# tqfp-sandwich-main.net
KiCad netlist of a schematic drawn in EAGLE
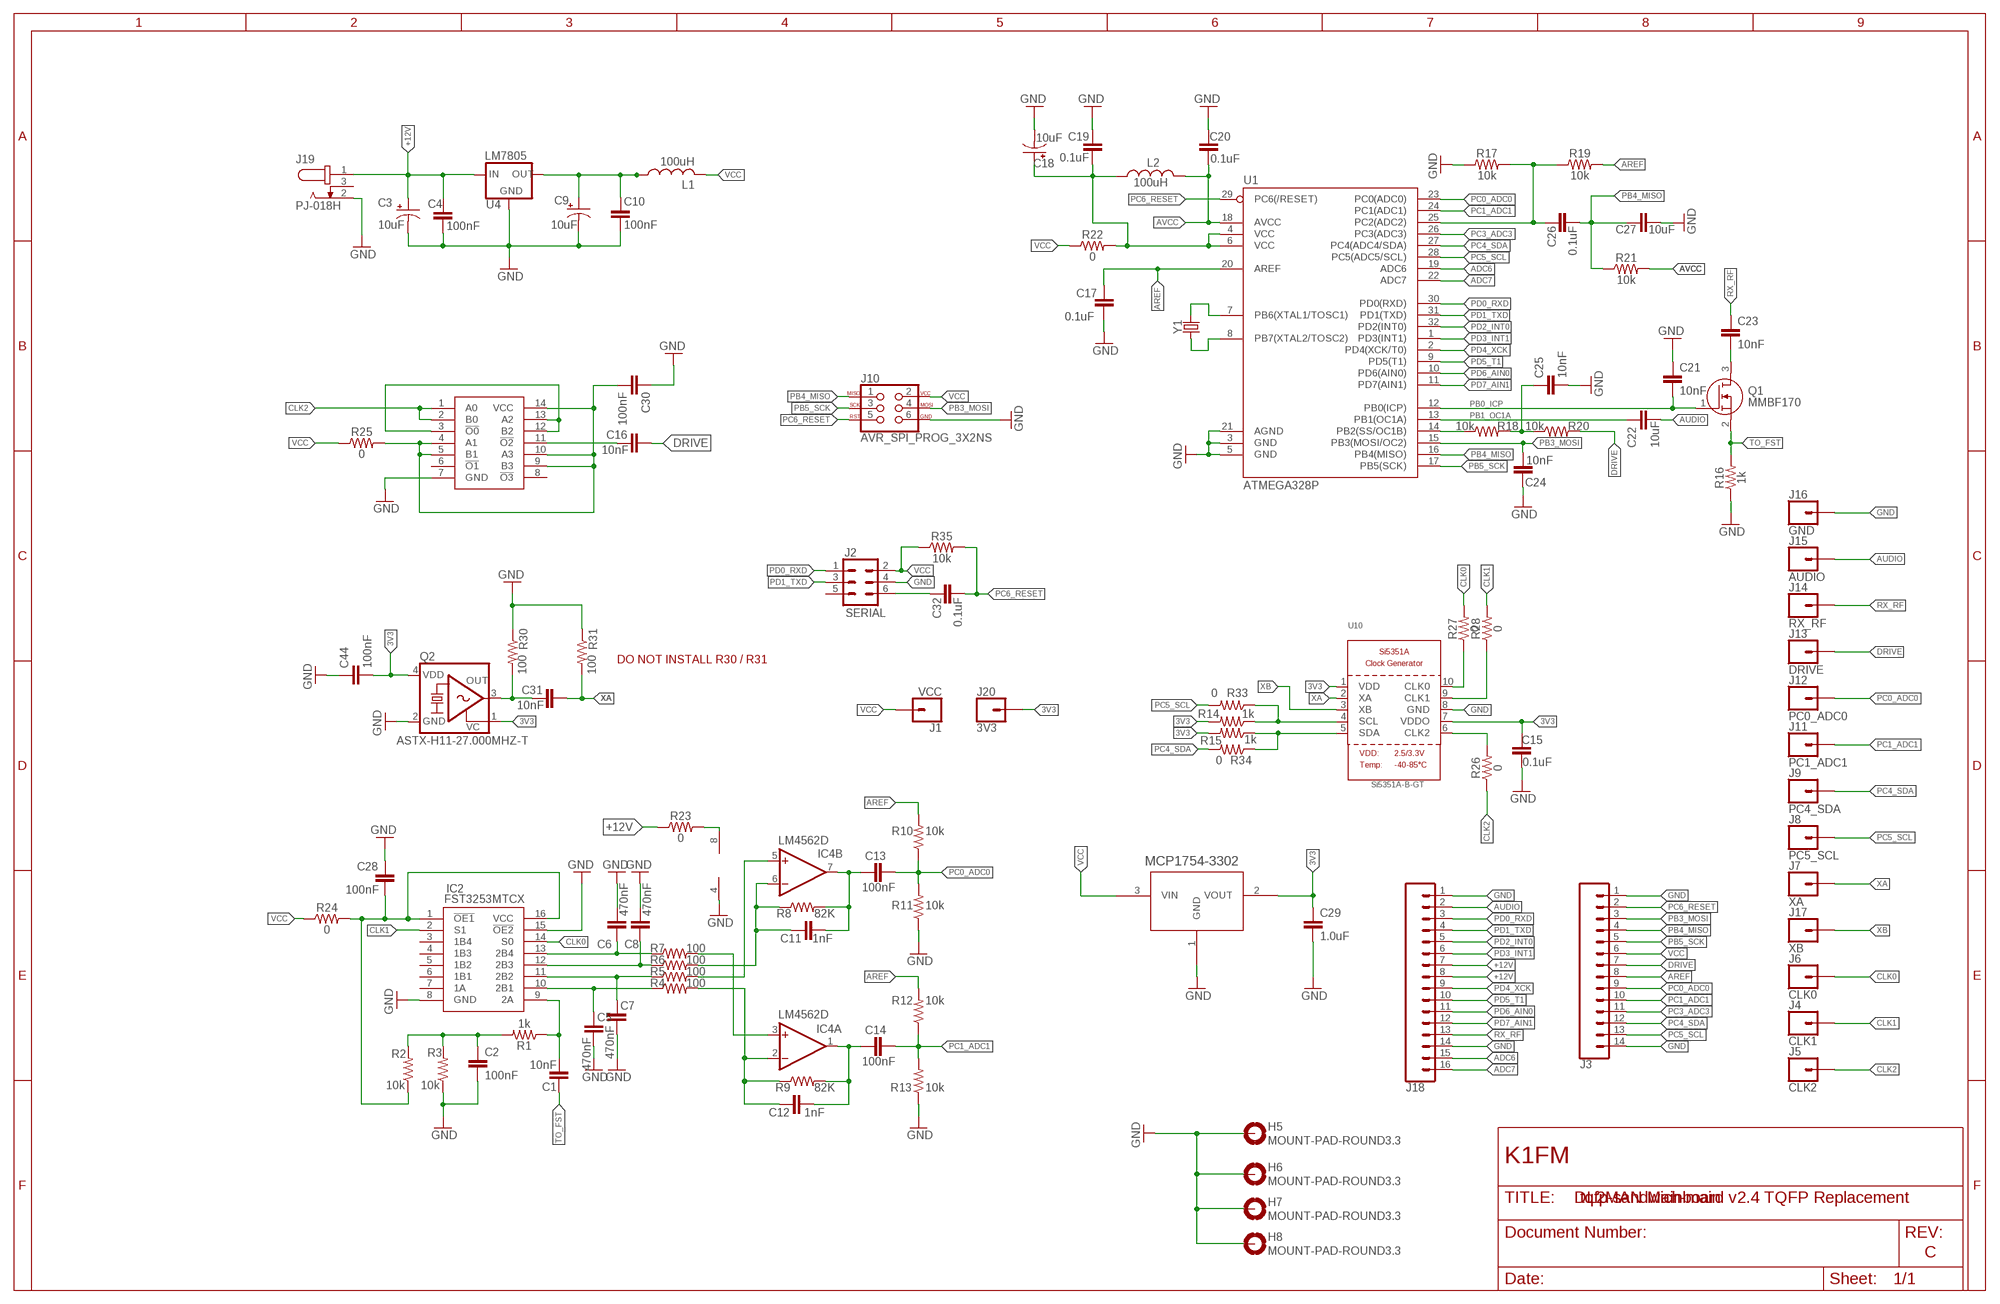
[diagram p0: schematic, sheet 1]

(export (version "E")
  (design (tool "Eeschema 10.0.6"))
  (components
    (comp (ref "C1")
      (value "10nF")
      (footprint "eagle-import:0603")
      (libsource (lib "eagle-import") (part "10NF-0603-50V-10%"))
    )
    (comp (ref "C2")
      (value "100nF")
      (footprint "eagle-import:0603")
      (libsource (lib "eagle-import") (part "10NF-0603-50V-10%"))
    )
    (comp (ref "C3")
      (value "10uF")
      (footprint "eagle-import:EIA3216")
      (libsource (lib "eagle-import") (part "10UF-POLAR-EIA3216-16V-10%(TANT)"))
    )
    (comp (ref "C4")
      (value "100nF")
      (footprint "eagle-import:0603")
      (libsource (lib "eagle-import") (part "10NF-0603-50V-10%"))
    )
    (comp (ref "C5")
      (value "470nF")
      (footprint "eagle-import:0603")
      (libsource (lib "eagle-import") (part "470PF-0603-50V-5%"))
    )
    (comp (ref "C6")
      (value "470nF")
      (footprint "eagle-import:0603")
      (libsource (lib "eagle-import") (part "470PF-0603-50V-5%"))
    )
    (comp (ref "C7")
      (value "470nF")
      (footprint "eagle-import:0603")
      (libsource (lib "eagle-import") (part "470PF-0603-50V-5%"))
    )
    (comp (ref "C8")
      (value "470nF")
      (footprint "eagle-import:0603")
      (libsource (lib "eagle-import") (part "470PF-0603-50V-5%"))
    )
    (comp (ref "C9")
      (value "10uF")
      (footprint "eagle-import:EIA3216")
      (libsource (lib "eagle-import") (part "10UF-POLAR-EIA3216-16V-10%(TANT)"))
    )
    (comp (ref "C10")
      (value "100nF")
      (footprint "eagle-import:0603")
      (libsource (lib "eagle-import") (part "10NF-0603-50V-10%"))
    )
    (comp (ref "C11")
      (value "1nF")
      (footprint "eagle-import:0603")
      (libsource (lib "eagle-import") (part "1.0NF/1000PF-0603-50V-10%"))
    )
    (comp (ref "C12")
      (value "1nF")
      (footprint "eagle-import:0603")
      (libsource (lib "eagle-import") (part "1.0NF/1000PF-0603-50V-10%"))
    )
    (comp (ref "C13")
      (value "100nF")
      (footprint "eagle-import:0603")
      (libsource (lib "eagle-import") (part "10NF-0603-50V-10%"))
    )
    (comp (ref "C14")
      (value "100nF")
      (footprint "eagle-import:0603")
      (libsource (lib "eagle-import") (part "10NF-0603-50V-10%"))
    )
    (comp (ref "C15")
      (value "0.1uF")
      (footprint "eagle-import:0603")
      (libsource (lib "eagle-import") (part "0.1UF-0603-25V-(+80/-20%)"))
    )
    (comp (ref "C16")
      (value "10nF")
      (footprint "eagle-import:0603")
      (libsource (lib "eagle-import") (part "10NF-0603-50V-10%"))
    )
    (comp (ref "C17")
      (value "0.1uF")
      (footprint "eagle-import:0603")
      (libsource (lib "eagle-import") (part "0.1UF-0603-25V-(+80/-20%)"))
    )
    (comp (ref "C18")
      (value "10uF")
      (footprint "eagle-import:EIA3216")
      (libsource (lib "eagle-import") (part "10UF-POLAR-EIA3216-16V-10%(TANT)"))
    )
    (comp (ref "C19")
      (value "0.1uF")
      (footprint "eagle-import:0603")
      (libsource (lib "eagle-import") (part "0.1UF-0603-25V-(+80/-20%)"))
    )
    (comp (ref "C20")
      (value "0.1uF")
      (footprint "eagle-import:0603")
      (libsource (lib "eagle-import") (part "0.1UF-0603-25V-(+80/-20%)"))
    )
    (comp (ref "C21")
      (value "10nF")
      (footprint "eagle-import:0603")
      (libsource (lib "eagle-import") (part "10NF-0603-50V-10%"))
    )
    (comp (ref "C22")
      (value "10uF")
      (footprint "eagle-import:0603")
      (libsource (lib "eagle-import") (part "10UF-0603-6.3V-20%"))
    )
    (comp (ref "C23")
      (value "10nF")
      (footprint "eagle-import:0603")
      (libsource (lib "eagle-import") (part "10NF-0603-50V-10%"))
    )
    (comp (ref "C24")
      (value "10nF")
      (footprint "eagle-import:0603")
      (libsource (lib "eagle-import") (part "10NF-0603-50V-10%"))
    )
    (comp (ref "C25")
      (value "10nF")
      (footprint "eagle-import:0603")
      (libsource (lib "eagle-import") (part "10NF-0603-50V-10%"))
    )
    (comp (ref "C26")
      (value "0.1uF")
      (footprint "eagle-import:0603")
      (libsource (lib "eagle-import") (part "0.1UF-0603-25V-(+80/-20%)"))
    )
    (comp (ref "C27")
      (value "10uF")
      (footprint "eagle-import:0603")
      (libsource (lib "eagle-import") (part "10NF-0603-50V-10%"))
    )
    (comp (ref "C28")
      (value "100nF")
      (footprint "eagle-import:0603")
      (libsource (lib "eagle-import") (part "10NF-0603-50V-10%"))
    )
    (comp (ref "C29")
      (value "1.0uF")
      (footprint "eagle-import:0603")
      (libsource (lib "eagle-import") (part "1.0UF-0603-16V-10%"))
    )
    (comp (ref "C30")
      (value "100nF")
      (footprint "eagle-import:0603")
      (libsource (lib "eagle-import") (part "10NF-0603-50V-10%"))
    )
    (comp (ref "C31")
      (value "10nF")
      (footprint "eagle-import:0603")
      (libsource (lib "eagle-import") (part "10NF-0603-50V-10%"))
    )
    (comp (ref "C32")
      (value "0.1uF")
      (footprint "eagle-import:0603")
      (libsource (lib "eagle-import") (part "0.1UF-0603-25V-(+80/-20%)"))
    )
    (comp (ref "C44")
      (value "100nF")
      (footprint "eagle-import:0603")
      (libsource (lib "eagle-import") (part "10NF-0603-50V-10%"))
    )
    (comp (ref "H5")
      (value "MOUNT-PAD-ROUND3.3")
      (footprint "eagle-import:3,3-PAD")
      (libsource (lib "eagle-import") (part "MOUNT-PAD-ROUND3.3"))
    )
    (comp (ref "H6")
      (value "MOUNT-PAD-ROUND3.3")
      (footprint "eagle-import:3,3-PAD")
      (libsource (lib "eagle-import") (part "MOUNT-PAD-ROUND3.3"))
    )
    (comp (ref "H7")
      (value "MOUNT-PAD-ROUND3.3")
      (footprint "eagle-import:3,3-PAD")
      (libsource (lib "eagle-import") (part "MOUNT-PAD-ROUND3.3"))
    )
    (comp (ref "H8")
      (value "MOUNT-PAD-ROUND3.3")
      (footprint "eagle-import:3,3-PAD")
      (libsource (lib "eagle-import") (part "MOUNT-PAD-ROUND3.3"))
    )
    (comp (ref "IC2")
      (value "FST3253MTCX")
      (footprint "eagle-import:SOP65P640X110-16N")
      (fields (field (name "MOUSER_PART_NUMBER") "512-FST3253MTCX"))
      (libsource (lib "eagle-import") (part "FST3253MTCX"))
    )
    (comp (ref "IC3")
      (value "74ACT00MTC")
      (footprint "eagle-import:SOP65P640X120-14N")
      (fields (field (name "MOUSER_PART_NUMBER") "512-74ACT00MTC"))
      (libsource (lib "eagle-import") (part "74ACT00MTC"))
    )
    (comp (ref "IC4")
      (value "LM4562D")
      (footprint "eagle-import:SO08")
      (libsource (lib "eagle-import") (part "LM4562D"))
    )
    (comp (ref "J1")
      (value "VCC")
      (footprint "eagle-import:1X01NS_KIT")
      (libsource (lib "eagle-import") (part "CONN_01PTH_NO_SILK_KIT"))
    )
    (comp (ref "J2")
      (value "SERIAL")
      (footprint "eagle-import:2X3")
      (libsource (lib "eagle-import") (part "CONN_03X2FEMALE"))
    )
    (comp (ref "J3")
      (value "CONN_14")
      (footprint "eagle-import:1X14")
      (libsource (lib "eagle-import") (part "CONN_14"))
    )
    (comp (ref "J4")
      (value "CLK1")
      (footprint "eagle-import:1X01_LONGPAD")
      (libsource (lib "eagle-import") (part "CONN_01PTH_LONGPAD"))
    )
    (comp (ref "J5")
      (value "CLK2")
      (footprint "eagle-import:1X01_LONGPAD")
      (libsource (lib "eagle-import") (part "CONN_01PTH_LONGPAD"))
    )
    (comp (ref "J6")
      (value "CLK0")
      (footprint "eagle-import:1X01_LONGPAD")
      (libsource (lib "eagle-import") (part "CONN_01PTH_LONGPAD"))
    )
    (comp (ref "J7")
      (value "XA")
      (footprint "eagle-import:1X01_LONGPAD")
      (libsource (lib "eagle-import") (part "CONN_01PTH_LONGPAD"))
    )
    (comp (ref "J8")
      (value "PC5_SCL")
      (footprint "eagle-import:1X01_LONGPAD")
      (libsource (lib "eagle-import") (part "CONN_01PTH_LONGPAD"))
    )
    (comp (ref "J9")
      (value "PC4_SDA")
      (footprint "eagle-import:1X01_LONGPAD")
      (libsource (lib "eagle-import") (part "CONN_01PTH_LONGPAD"))
    )
    (comp (ref "J10")
      (value "AVR_SPI_PROG_3X2NS")
      (footprint "eagle-import:2X3-NS")
      (libsource (lib "eagle-import") (part "AVR_SPI_PROG_3X2NS"))
    )
    (comp (ref "J11")
      (value "PC1_ADC1")
      (footprint "eagle-import:1X01_LONGPAD")
      (libsource (lib "eagle-import") (part "CONN_01PTH_LONGPAD"))
    )
    (comp (ref "J12")
      (value "PC0_ADC0")
      (footprint "eagle-import:1X01_LONGPAD")
      (libsource (lib "eagle-import") (part "CONN_01PTH_LONGPAD"))
    )
    (comp (ref "J13")
      (value "DRIVE")
      (footprint "eagle-import:1X01_LONGPAD")
      (libsource (lib "eagle-import") (part "CONN_01PTH_LONGPAD"))
    )
    (comp (ref "J14")
      (value "RX_RF")
      (footprint "eagle-import:1X01_LONGPAD")
      (libsource (lib "eagle-import") (part "CONN_01PTH_LONGPAD"))
    )
    (comp (ref "J15")
      (value "AUDIO")
      (footprint "eagle-import:1X01_LONGPAD")
      (libsource (lib "eagle-import") (part "CONN_01PTH_LONGPAD"))
    )
    (comp (ref "J16")
      (value "GND")
      (footprint "eagle-import:1X01_LONGPAD")
      (libsource (lib "eagle-import") (part "CONN_01PTH_LONGPAD"))
    )
    (comp (ref "J17")
      (value "XB")
      (footprint "eagle-import:1X01_LONGPAD")
      (libsource (lib "eagle-import") (part "CONN_01PTH_LONGPAD"))
    )
    (comp (ref "J18")
      (value "CONN_16")
      (footprint "eagle-import:1X16")
      (libsource (lib "eagle-import") (part "CONN_16"))
    )
    (comp (ref "J19")
      (value "PJ-018H")
      (footprint "eagle-import:CUI_PJ-018H")
      (fields (field (name "MANUFACTURER") "CUI INC"))
      (libsource (lib "eagle-import") (part "PJ-018H"))
    )
    (comp (ref "J20")
      (value "3V3")
      (footprint "eagle-import:1X01NS_KIT")
      (libsource (lib "eagle-import") (part "CONN_01PTH_NO_SILK_KIT"))
    )
    (comp (ref "L1")
      (value "100uH")
      (footprint "eagle-import:RESC0805_L")
      (libsource (lib "eagle-import") (part "INDUCTOR_0805_L"))
    )
    (comp (ref "L2")
      (value "100uH")
      (footprint "eagle-import:RESC0805_L")
      (libsource (lib "eagle-import") (part "INDUCTOR_0805_L"))
    )
    (comp (ref "Q1")
      (value "MMBF170")
      (footprint "eagle-import:SOT96P237X111-3N")
      (fields (field (name "MOUSER_PART_NUMBER") "512-MMBF170"))
      (libsource (lib "eagle-import") (part "MMBF170"))
    )
    (comp (ref "Q2")
      (value "ASTX-H11-27.000MHZ-T")
      (footprint "eagle-import:3.2X2.5_KXO-84")
      (libsource (lib "eagle-import") (part "KXO-VCXO-SINE-84"))
    )
    (comp (ref "R1")
      (value "1k")
      (footprint "eagle-import:0603")
      (libsource (lib "eagle-import") (part "1KOHM-0603-1/10W-1%"))
    )
    (comp (ref "R2")
      (value "10k")
      (footprint "eagle-import:0603")
      (libsource (lib "eagle-import") (part "10KOHM-0603-1/10W-1%"))
    )
    (comp (ref "R3")
      (value "10k")
      (footprint "eagle-import:0603")
      (libsource (lib "eagle-import") (part "10KOHM-0603-1/10W-1%"))
    )
    (comp (ref "R4")
      (value "100")
      (footprint "eagle-import:0603")
      (libsource (lib "eagle-import") (part "100OHM-0603-1/4W-5%"))
    )
    (comp (ref "R5")
      (value "100")
      (footprint "eagle-import:0603")
      (libsource (lib "eagle-import") (part "100OHM-0603-1/4W-5%"))
    )
    (comp (ref "R6")
      (value "100")
      (footprint "eagle-import:0603")
      (libsource (lib "eagle-import") (part "100OHM-0603-1/4W-5%"))
    )
    (comp (ref "R7")
      (value "100")
      (footprint "eagle-import:0603")
      (libsource (lib "eagle-import") (part "100OHM-0603-1/4W-5%"))
    )
    (comp (ref "R8")
      (value "82K")
      (footprint "eagle-import:0603")
      (libsource (lib "eagle-import") (part "82OHM-0603-1/10W-1%"))
    )
    (comp (ref "R9")
      (value "82K")
      (footprint "eagle-import:0603")
      (libsource (lib "eagle-import") (part "82OHM-0603-1/10W-1%"))
    )
    (comp (ref "R10")
      (value "10k")
      (footprint "eagle-import:0603")
      (libsource (lib "eagle-import") (part "10KOHM-0603-1/10W-1%"))
    )
    (comp (ref "R11")
      (value "10k")
      (footprint "eagle-import:0603")
      (libsource (lib "eagle-import") (part "10KOHM-0603-1/10W-1%"))
    )
    (comp (ref "R12")
      (value "10k")
      (footprint "eagle-import:0603")
      (libsource (lib "eagle-import") (part "10KOHM-0603-1/10W-1%"))
    )
    (comp (ref "R13")
      (value "10k")
      (footprint "eagle-import:0603")
      (libsource (lib "eagle-import") (part "10KOHM-0603-1/10W-1%"))
    )
    (comp (ref "R14")
      (value "1k")
      (footprint "eagle-import:0603")
      (libsource (lib "eagle-import") (part "1KOHM-0603-1/10W-1%"))
    )
    (comp (ref "R15")
      (value "1k")
      (footprint "eagle-import:0603")
      (libsource (lib "eagle-import") (part "1KOHM-0603-1/10W-1%"))
    )
    (comp (ref "R16")
      (value "1k")
      (footprint "eagle-import:0603")
      (libsource (lib "eagle-import") (part "1KOHM-0603-1/10W-1%"))
    )
    (comp (ref "R17")
      (value "10k")
      (footprint "eagle-import:0603")
      (libsource (lib "eagle-import") (part "10KOHM-0603-1/10W-1%"))
    )
    (comp (ref "R18")
      (value "10k")
      (footprint "eagle-import:0603")
      (libsource (lib "eagle-import") (part "10KOHM-0603-1/10W-1%"))
    )
    (comp (ref "R19")
      (value "10k")
      (footprint "eagle-import:0603")
      (libsource (lib "eagle-import") (part "10KOHM-0603-1/10W-1%"))
    )
    (comp (ref "R20")
      (value "10k")
      (footprint "eagle-import:0603")
      (libsource (lib "eagle-import") (part "10KOHM-0603-1/10W-1%"))
    )
    (comp (ref "R21")
      (value "10k")
      (footprint "eagle-import:0603")
      (libsource (lib "eagle-import") (part "10KOHM-0603-1/10W-1%"))
    )
    (comp (ref "R22")
      (value "0")
      (footprint "eagle-import:0603")
      (libsource (lib "eagle-import") (part "0OHM-0603-1/10W-5%"))
    )
    (comp (ref "R23")
      (value "0")
      (footprint "eagle-import:0603")
      (libsource (lib "eagle-import") (part "0OHM-0603-1/10W-5%"))
    )
    (comp (ref "R24")
      (value "0")
      (footprint "eagle-import:0603")
      (libsource (lib "eagle-import") (part "0OHM-0603-1/10W-5%"))
    )
    (comp (ref "R25")
      (value "0")
      (footprint "eagle-import:0603")
      (libsource (lib "eagle-import") (part "0OHM-0603-1/10W-5%"))
    )
    (comp (ref "R26")
      (value "0")
      (footprint "eagle-import:0603")
      (libsource (lib "eagle-import") (part "0OHM-0603-1/10W-5%"))
    )
    (comp (ref "R27")
      (value "0")
      (footprint "eagle-import:0603")
      (libsource (lib "eagle-import") (part "0OHM-0603-1/10W-5%"))
    )
    (comp (ref "R28")
      (value "0")
      (footprint "eagle-import:0603")
      (libsource (lib "eagle-import") (part "0OHM-0603-1/10W-5%"))
    )
    (comp (ref "R30")
      (value "100")
      (footprint "eagle-import:0603")
      (libsource (lib "eagle-import") (part "1KOHM-0603-1/10W-1%"))
    )
    (comp (ref "R31")
      (value "100")
      (footprint "eagle-import:0603")
      (libsource (lib "eagle-import") (part "1KOHM-0603-1/10W-1%"))
    )
    (comp (ref "R33")
      (value "0")
      (footprint "eagle-import:0603")
      (libsource (lib "eagle-import") (part "0OHM-0603-1/10W-5%"))
    )
    (comp (ref "R34")
      (value "0")
      (footprint "eagle-import:0603")
      (libsource (lib "eagle-import") (part "0OHM-0603-1/10W-5%"))
    )
    (comp (ref "R35")
      (value "10k")
      (footprint "eagle-import:0603")
      (libsource (lib "eagle-import") (part "10KOHM-0603-1/10W-1%"))
    )
    (comp (ref "U1")
      (value "ATMEGA328P")
      (footprint "eagle-import:TQFP32-08")
      (libsource (lib "eagle-import") (part "ATMEGA328P_TQFP"))
    )
    (comp (ref "U3")
      (value "MCP1754X-XXXXX/C")
      (footprint "eagle-import:SOT-23A_MC")
      (libsource (lib "eagle-import") (part "MCP1754X-XXXXX/C"))
    )
    (comp (ref "U4")
      (value "LM7805")
      (footprint "eagle-import:TO-252")
      (libsource (lib "eagle-import") (part "V_REG_78XX7812"))
    )
    (comp (ref "U10")
      (value "Si5351A-B-GT")
      (footprint "eagle-import:MSOP10")
      (libsource (lib "eagle-import") (part "SI5351A"))
    )
    (comp (ref "Y1")
      (value "CRYSTALSMD-5X3.2-2PAD")
      (footprint "eagle-import:CRYSTAL-SMD-5X3.2-2PAD")
      (libsource (lib "eagle-import") (part "CRYSTALSMD-5X3.2-2PAD"))
    )
  )
  (nets
    (net (code "1") (name "+12V") (class "Default")
      (node (ref "C3") (pin "+") (pinfunction "+_+") (pintype "passive"))
      (node (ref "C4") (pin "2") (pinfunction "2_2") (pintype "passive"))
      (node (ref "J18") (pin "7") (pinfunction "7_7") (pintype "passive"))
      (node (ref "J18") (pin "8") (pinfunction "8_8") (pintype "passive"))
      (node (ref "J19") (pin "1") (pinfunction "1_1") (pintype "passive"))
      (node (ref "R23") (pin "1") (pinfunction "1_1") (pintype "passive"))
      (node (ref "U4") (pin "1") (pinfunction "IN_1") (pintype "input"))
    )
    (net (code "2") (name "/PB0_ICP") (class "Default")
      (node (ref "C21") (pin "2") (pinfunction "2_2") (pintype "passive"))
      (node (ref "Q1") (pin "1") (pinfunction "G_1") (pintype "bidirectional"))
      (node (ref "U1") (pin "12") (pinfunction "PB0(ICP)_12") (pintype "bidirectional"))
    )
    (net (code "3") (name "/PB1_OC1A") (class "Default")
      (node (ref "C22") (pin "1") (pinfunction "1_1") (pintype "passive"))
      (node (ref "U1") (pin "13") (pinfunction "PB1(OC1A)_13") (pintype "bidirectional"))
    )
    (net (code "4") (name "3V3") (class "Default")
      (node (ref "C15") (pin "2") (pinfunction "2_2") (pintype "passive"))
      (node (ref "C29") (pin "1") (pinfunction "1_1") (pintype "passive"))
      (node (ref "C44") (pin "2") (pinfunction "2_2") (pintype "passive"))
      (node (ref "J20") (pin "1") (pinfunction "1_1") (pintype "passive"))
      (node (ref "Q2") (pin "1") (pinfunction "VC_1") (pintype "input"))
      (node (ref "Q2") (pin "4") (pinfunction "VDD_4") (pintype "power_in"))
      (node (ref "R14") (pin "2") (pinfunction "2_2") (pintype "passive"))
      (node (ref "R15") (pin "2") (pinfunction "2_2") (pintype "passive"))
      (node (ref "U10") (pin "1") (pinfunction "VDD_1") (pintype "power_in"))
      (node (ref "U10") (pin "7") (pinfunction "VDDO_7") (pintype "power_in"))
      (node (ref "U3") (pin "2") (pinfunction "VOUT_2") (pintype "passive"))
    )
    (net (code "5") (name "ADC6") (class "Default")
      (node (ref "J18") (pin "15") (pinfunction "15_15") (pintype "passive"))
      (node (ref "U1") (pin "19") (pinfunction "ADC6_19") (pintype "bidirectional"))
    )
    (net (code "6") (name "ADC7") (class "Default")
      (node (ref "J18") (pin "16") (pinfunction "16_16") (pintype "passive"))
      (node (ref "U1") (pin "22") (pinfunction "ADC7_22") (pintype "bidirectional"))
    )
    (net (code "7") (name "AREF") (class "Default")
      (node (ref "C17") (pin "2") (pinfunction "2_2") (pintype "passive"))
      (node (ref "J3") (pin "8") (pinfunction "8_8") (pintype "passive"))
      (node (ref "R10") (pin "2") (pinfunction "2_2") (pintype "passive"))
      (node (ref "R12") (pin "2") (pinfunction "2_2") (pintype "passive"))
      (node (ref "R19") (pin "2") (pinfunction "2_2") (pintype "passive"))
      (node (ref "U1") (pin "20") (pinfunction "AREF_20") (pintype "bidirectional"))
    )
    (net (code "8") (name "AUDIO") (class "Default")
      (node (ref "C22") (pin "2") (pinfunction "2_2") (pintype "passive"))
      (node (ref "J15") (pin "1") (pinfunction "1_1") (pintype "passive"))
      (node (ref "J18") (pin "2") (pinfunction "2_2") (pintype "passive"))
    )
    (net (code "9") (name "AVCC") (class "Default")
      (node (ref "C20") (pin "1") (pinfunction "1_1") (pintype "passive"))
      (node (ref "L2") (pin "2") (pinfunction "2_2") (pintype "passive"))
      (node (ref "R21") (pin "2") (pinfunction "2_2") (pintype "passive"))
      (node (ref "U1") (pin "18") (pinfunction "AVCC_18") (pintype "bidirectional"))
    )
    (net (code "10") (name "CLK0") (class "Default")
      (node (ref "IC2") (pin "14") (pinfunction "S0_14") (pintype "bidirectional"))
      (node (ref "J6") (pin "1") (pinfunction "1_1") (pintype "passive"))
      (node (ref "R27") (pin "2") (pinfunction "2_2") (pintype "passive"))
    )
    (net (code "11") (name "CLK1") (class "Default")
      (node (ref "IC2") (pin "2") (pinfunction "S1_2") (pintype "bidirectional"))
      (node (ref "J4") (pin "1") (pinfunction "1_1") (pintype "passive"))
      (node (ref "R28") (pin "2") (pinfunction "2_2") (pintype "passive"))
    )
    (net (code "12") (name "CLK2") (class "Default")
      (node (ref "IC3") (pin "1") (pinfunction "A0_1") (pintype "bidirectional"))
      (node (ref "IC3") (pin "2") (pinfunction "B0_2") (pintype "bidirectional"))
      (node (ref "J5") (pin "1") (pinfunction "1_1") (pintype "passive"))
      (node (ref "R26") (pin "1") (pinfunction "1_1") (pintype "passive"))
    )
    (net (code "13") (name "DRIVE") (class "Default")
      (node (ref "C16") (pin "2") (pinfunction "2_2") (pintype "passive"))
      (node (ref "J13") (pin "1") (pinfunction "1_1") (pintype "passive"))
      (node (ref "J3") (pin "7") (pinfunction "7_7") (pintype "passive"))
      (node (ref "R20") (pin "2") (pinfunction "2_2") (pintype "passive"))
    )
    (net (code "14") (name "GND") (class "Default")
      (node (ref "C10") (pin "1") (pinfunction "1_1") (pintype "passive"))
      (node (ref "C15") (pin "1") (pinfunction "1_1") (pintype "passive"))
      (node (ref "C17") (pin "1") (pinfunction "1_1") (pintype "passive"))
      (node (ref "C18") (pin "-") (pinfunction "-_-") (pintype "passive"))
      (node (ref "C19") (pin "2") (pinfunction "2_2") (pintype "passive"))
      (node (ref "C2") (pin "2") (pinfunction "2_2") (pintype "passive"))
      (node (ref "C20") (pin "2") (pinfunction "2_2") (pintype "passive"))
      (node (ref "C21") (pin "1") (pinfunction "1_1") (pintype "passive"))
      (node (ref "C24") (pin "1") (pinfunction "1_1") (pintype "passive"))
      (node (ref "C25") (pin "2") (pinfunction "2_2") (pintype "passive"))
      (node (ref "C27") (pin "2") (pinfunction "2_2") (pintype "passive"))
      (node (ref "C28") (pin "1") (pinfunction "1_1") (pintype "passive"))
      (node (ref "C29") (pin "2") (pinfunction "2_2") (pintype "passive"))
      (node (ref "C3") (pin "-") (pinfunction "-_-") (pintype "passive"))
      (node (ref "C30") (pin "1") (pinfunction "1_1") (pintype "passive"))
      (node (ref "C4") (pin "1") (pinfunction "1_1") (pintype "passive"))
      (node (ref "C44") (pin "1") (pinfunction "1_1") (pintype "passive"))
      (node (ref "C5") (pin "2") (pinfunction "2_2") (pintype "passive"))
      (node (ref "C6") (pin "2") (pinfunction "2_2") (pintype "passive"))
      (node (ref "C7") (pin "2") (pinfunction "2_2") (pintype "passive"))
      (node (ref "C8") (pin "2") (pinfunction "2_2") (pintype "passive"))
      (node (ref "C9") (pin "-") (pinfunction "-_-") (pintype "passive"))
      (node (ref "H5") (pin "B3,3") (pinfunction "MOUNT_B3,3") (pintype "passive"))
      (node (ref "H6") (pin "B3,3") (pinfunction "MOUNT_B3,3") (pintype "passive"))
      (node (ref "H7") (pin "B3,3") (pinfunction "MOUNT_B3,3") (pintype "passive"))
      (node (ref "H8") (pin "B3,3") (pinfunction "MOUNT_B3,3") (pintype "passive"))
      (node (ref "IC2") (pin "15") (pinfunction "~{OE2}_15") (pintype "bidirectional"))
      (node (ref "IC2") (pin "8") (pinfunction "GND_8") (pintype "power_in"))
      (node (ref "IC3") (pin "7") (pinfunction "GND_7") (pintype "bidirectional"))
      (node (ref "IC4") (pin "4") (pinfunction "V-_4") (pintype "power_in"))
      (node (ref "J10") (pin "6") (pinfunction "6_6") (pintype "passive"))
      (node (ref "J16") (pin "1") (pinfunction "1_1") (pintype "passive"))
      (node (ref "J18") (pin "1") (pinfunction "1_1") (pintype "passive"))
      (node (ref "J18") (pin "14") (pinfunction "14_14") (pintype "passive"))
      (node (ref "J19") (pin "2") (pinfunction "2_2") (pintype "passive"))
      (node (ref "J2") (pin "4") (pinfunction "4_4") (pintype "bidirectional"))
      (node (ref "J3") (pin "1") (pinfunction "1_1") (pintype "passive"))
      (node (ref "J3") (pin "14") (pinfunction "14_14") (pintype "passive"))
      (node (ref "Q2") (pin "2") (pinfunction "GND_2") (pintype "power_in"))
      (node (ref "R11") (pin "1") (pinfunction "1_1") (pintype "passive"))
      (node (ref "R13") (pin "1") (pinfunction "1_1") (pintype "passive"))
      (node (ref "R16") (pin "1") (pinfunction "1_1") (pintype "passive"))
      (node (ref "R17") (pin "1") (pinfunction "1_1") (pintype "passive"))
      (node (ref "R3") (pin "1") (pinfunction "1_1") (pintype "passive"))
      (node (ref "R30") (pin "1") (pinfunction "1_1") (pintype "passive"))
      (node (ref "R31") (pin "1") (pinfunction "1_1") (pintype "passive"))
      (node (ref "U1") (pin "21") (pinfunction "AGND_21") (pintype "bidirectional"))
      (node (ref "U1") (pin "3") (pinfunction "GND_3") (pintype "bidirectional"))
      (node (ref "U1") (pin "5") (pinfunction "GND_5") (pintype "bidirectional"))
      (node (ref "U10") (pin "8") (pinfunction "GND_8") (pintype "power_in"))
      (node (ref "U3") (pin "1") (pinfunction "GND_1") (pintype "passive"))
      (node (ref "U4") (pin "3") (pinfunction "GND_3") (pintype "input"))
    )
    (net (code "15") (name "Net-(C2-Pad1)") (class "Default")
      (node (ref "C2") (pin "1") (pinfunction "1_1") (pintype "passive"))
      (node (ref "R1") (pin "2") (pinfunction "2_2") (pintype "passive"))
      (node (ref "R2") (pin "2") (pinfunction "2_2") (pintype "passive"))
      (node (ref "R3") (pin "2") (pinfunction "2_2") (pintype "passive"))
    )
    (net (code "16") (name "Net-(C18-Pad+)") (class "Default")
      (node (ref "C18") (pin "+") (pinfunction "+_+") (pintype "passive"))
      (node (ref "C19") (pin "1") (pinfunction "1_1") (pintype "passive"))
      (node (ref "L2") (pin "1") (pinfunction "1_1") (pintype "passive"))
      (node (ref "R22") (pin "2") (pinfunction "2_2") (pintype "passive"))
      (node (ref "U1") (pin "4") (pinfunction "VCC_4") (pintype "bidirectional"))
      (node (ref "U1") (pin "6") (pinfunction "VCC_6") (pintype "bidirectional"))
    )
    (net (code "17") (name "Net-(C25-Pad1)") (class "Default")
      (node (ref "C25") (pin "1") (pinfunction "1_1") (pintype "passive"))
      (node (ref "R18") (pin "2") (pinfunction "2_2") (pintype "passive"))
      (node (ref "R20") (pin "1") (pinfunction "1_1") (pintype "passive"))
    )
    (net (code "18") (name "Net-(C32-Pad2)") (class "Default")
      (node (ref "C32") (pin "2") (pinfunction "2_2") (pintype "passive"))
      (node (ref "J2") (pin "6") (pinfunction "6_6") (pintype "bidirectional"))
    )
    (net (code "19") (name "Net-(IC2-2A)") (class "Default")
      (node (ref "C1") (pin "2") (pinfunction "2_2") (pintype "passive"))
      (node (ref "IC2") (pin "9") (pinfunction "2A_9") (pintype "bidirectional"))
      (node (ref "R1") (pin "1") (pinfunction "1_1") (pintype "passive"))
    )
    (net (code "20") (name "Net-(IC2-2B1)") (class "Default")
      (node (ref "C5") (pin "1") (pinfunction "1_1") (pintype "passive"))
      (node (ref "IC2") (pin "10") (pinfunction "2B1_10") (pintype "bidirectional"))
      (node (ref "R4") (pin "1") (pinfunction "1_1") (pintype "passive"))
    )
    (net (code "21") (name "Net-(IC2-2B2)") (class "Default")
      (node (ref "C7") (pin "1") (pinfunction "1_1") (pintype "passive"))
      (node (ref "IC2") (pin "11") (pinfunction "2B2_11") (pintype "bidirectional"))
      (node (ref "R5") (pin "1") (pinfunction "1_1") (pintype "passive"))
    )
    (net (code "22") (name "Net-(IC2-2B3)") (class "Default")
      (node (ref "C8") (pin "1") (pinfunction "1_1") (pintype "passive"))
      (node (ref "IC2") (pin "12") (pinfunction "2B3_12") (pintype "bidirectional"))
      (node (ref "R6") (pin "1") (pinfunction "1_1") (pintype "passive"))
    )
    (net (code "23") (name "Net-(IC2-2B4)") (class "Default")
      (node (ref "C6") (pin "1") (pinfunction "1_1") (pintype "passive"))
      (node (ref "IC2") (pin "13") (pinfunction "2B4_13") (pintype "bidirectional"))
      (node (ref "R7") (pin "1") (pinfunction "1_1") (pintype "passive"))
    )
    (net (code "24") (name "Net-(IC2-VCC)") (class "Default")
      (node (ref "C28") (pin "2") (pinfunction "2_2") (pintype "passive"))
      (node (ref "IC2") (pin "1") (pinfunction "~{OE1}_1") (pintype "bidirectional"))
      (node (ref "IC2") (pin "16") (pinfunction "VCC_16") (pintype "power_in"))
      (node (ref "R2") (pin "1") (pinfunction "1_1") (pintype "passive"))
      (node (ref "R24") (pin "2") (pinfunction "2_2") (pintype "passive"))
    )
    (net (code "25") (name "Net-(IC3-A1)") (class "Default")
      (node (ref "C30") (pin "2") (pinfunction "2_2") (pintype "passive"))
      (node (ref "IC3") (pin "10") (pinfunction "A3_10") (pintype "bidirectional"))
      (node (ref "IC3") (pin "14") (pinfunction "VCC_14") (pintype "bidirectional"))
      (node (ref "IC3") (pin "4") (pinfunction "A1_4") (pintype "bidirectional"))
      (node (ref "IC3") (pin "5") (pinfunction "B1_5") (pintype "bidirectional"))
      (node (ref "IC3") (pin "9") (pinfunction "B3_9") (pintype "bidirectional"))
      (node (ref "R25") (pin "2") (pinfunction "2_2") (pintype "passive"))
    )
    (net (code "26") (name "Net-(IC3-A2)") (class "Default")
      (node (ref "IC3") (pin "12") (pinfunction "B2_12") (pintype "bidirectional"))
      (node (ref "IC3") (pin "13") (pinfunction "A2_13") (pintype "bidirectional"))
      (node (ref "IC3") (pin "3") (pinfunction "~{O0}_3") (pintype "bidirectional"))
    )
    (net (code "27") (name "Net-(IC3-~{O2})") (class "Default")
      (node (ref "C16") (pin "1") (pinfunction "1_1") (pintype "passive"))
      (node (ref "IC3") (pin "11") (pinfunction "~{O2}_11") (pintype "bidirectional"))
    )
    (net (code "28") (name "Net-(IC4A-+IN)") (class "Default")
      (node (ref "IC4") (pin "3") (pinfunction "+IN_3") (pintype "input"))
      (node (ref "R7") (pin "2") (pinfunction "2_2") (pintype "passive"))
    )
    (net (code "29") (name "Net-(IC4A--IN)") (class "Default")
      (node (ref "C12") (pin "1") (pinfunction "1_1") (pintype "passive"))
      (node (ref "IC4") (pin "2") (pinfunction "-IN_2") (pintype "input"))
      (node (ref "R4") (pin "2") (pinfunction "2_2") (pintype "passive"))
      (node (ref "R9") (pin "1") (pinfunction "1_1") (pintype "passive"))
    )
    (net (code "30") (name "Net-(IC4A-OUT)") (class "Default")
      (node (ref "C12") (pin "2") (pinfunction "2_2") (pintype "passive"))
      (node (ref "C14") (pin "1") (pinfunction "1_1") (pintype "passive"))
      (node (ref "IC4") (pin "1") (pinfunction "OUT_1") (pintype "output"))
      (node (ref "R9") (pin "2") (pinfunction "2_2") (pintype "passive"))
    )
    (net (code "31") (name "Net-(IC4B-+IN)") (class "Default")
      (node (ref "IC4") (pin "5") (pinfunction "+IN_5") (pintype "input"))
      (node (ref "R5") (pin "2") (pinfunction "2_2") (pintype "passive"))
    )
    (net (code "32") (name "Net-(IC4B--IN)") (class "Default")
      (node (ref "C11") (pin "1") (pinfunction "1_1") (pintype "passive"))
      (node (ref "IC4") (pin "6") (pinfunction "-IN_6") (pintype "input"))
      (node (ref "R6") (pin "2") (pinfunction "2_2") (pintype "passive"))
      (node (ref "R8") (pin "1") (pinfunction "1_1") (pintype "passive"))
    )
    (net (code "33") (name "Net-(IC4B-OUT)") (class "Default")
      (node (ref "C11") (pin "2") (pinfunction "2_2") (pintype "passive"))
      (node (ref "C13") (pin "1") (pinfunction "1_1") (pintype "passive"))
      (node (ref "IC4") (pin "7") (pinfunction "OUT_7") (pintype "output"))
      (node (ref "R8") (pin "2") (pinfunction "2_2") (pintype "passive"))
    )
    (net (code "34") (name "Net-(IC4C-V+)") (class "Default")
      (node (ref "IC4") (pin "8") (pinfunction "V+_8") (pintype "power_in"))
      (node (ref "R23") (pin "2") (pinfunction "2_2") (pintype "passive"))
    )
    (net (code "35") (name "Net-(Q1-D)") (class "Default")
      (node (ref "C23") (pin "2") (pinfunction "2_2") (pintype "passive"))
      (node (ref "Q1") (pin "3") (pinfunction "D_3") (pintype "bidirectional"))
    )
    (net (code "36") (name "Net-(Q2-OUT)") (class "Default")
      (node (ref "C31") (pin "1") (pinfunction "1_1") (pintype "passive"))
      (node (ref "Q2") (pin "3") (pinfunction "OUT_3") (pintype "output"))
      (node (ref "R30") (pin "2") (pinfunction "2_2") (pintype "passive"))
    )
    (net (code "37") (name "Net-(U1-PB2(SS{slash}OC1B))") (class "Default")
      (node (ref "R18") (pin "1") (pinfunction "1_1") (pintype "passive"))
      (node (ref "U1") (pin "14") (pinfunction "PB2(SS/OC1B)_14") (pintype "bidirectional"))
    )
    (net (code "38") (name "Net-(U1-PB6(XTAL1{slash}TOSC1))") (class "Default")
      (node (ref "U1") (pin "7") (pinfunction "PB6(XTAL1/TOSC1)_7") (pintype "bidirectional"))
      (node (ref "Y1") (pin "P$2") (pinfunction "2_P$2") (pintype "passive"))
    )
    (net (code "39") (name "Net-(U1-PB7(XTAL2{slash}TOSC2))") (class "Default")
      (node (ref "U1") (pin "8") (pinfunction "PB7(XTAL2/TOSC2)_8") (pintype "bidirectional"))
      (node (ref "Y1") (pin "P$1") (pinfunction "1_P$1") (pintype "passive"))
    )
    (net (code "40") (name "Net-(U1-PC2(ADC2))") (class "Default")
      (node (ref "C26") (pin "2") (pinfunction "2_2") (pintype "passive"))
      (node (ref "R17") (pin "2") (pinfunction "2_2") (pintype "passive"))
      (node (ref "R19") (pin "1") (pinfunction "1_1") (pintype "passive"))
      (node (ref "U1") (pin "25") (pinfunction "PC2(ADC2)_25") (pintype "bidirectional"))
    )
    (net (code "41") (name "Net-(U4-OUT)") (class "Default")
      (node (ref "C10") (pin "2") (pinfunction "2_2") (pintype "passive"))
      (node (ref "C9") (pin "+") (pinfunction "+_+") (pintype "passive"))
      (node (ref "L1") (pin "1") (pinfunction "1_1") (pintype "passive"))
      (node (ref "U4") (pin "2") (pinfunction "OUT_2") (pintype "passive"))
    )
    (net (code "42") (name "Net-(U10-CLK0)") (class "Default")
      (node (ref "R27") (pin "1") (pinfunction "1_1") (pintype "passive"))
      (node (ref "U10") (pin "10") (pinfunction "CLK0_10") (pintype "output"))
    )
    (net (code "43") (name "Net-(U10-CLK1)") (class "Default")
      (node (ref "R28") (pin "1") (pinfunction "1_1") (pintype "passive"))
      (node (ref "U10") (pin "9") (pinfunction "CLK1_9") (pintype "output"))
    )
    (net (code "44") (name "Net-(U10-CLK2)") (class "Default")
      (node (ref "R26") (pin "2") (pinfunction "2_2") (pintype "passive"))
      (node (ref "U10") (pin "6") (pinfunction "CLK2_6") (pintype "output"))
    )
    (net (code "45") (name "Net-(U10-SCL)") (class "Default")
      (node (ref "R14") (pin "1") (pinfunction "1_1") (pintype "passive"))
      (node (ref "R33") (pin "1") (pinfunction "1_1") (pintype "passive"))
      (node (ref "U10") (pin "4") (pinfunction "SCL_4") (pintype "input"))
    )
    (net (code "46") (name "Net-(U10-SDA)") (class "Default")
      (node (ref "R15") (pin "1") (pinfunction "1_1") (pintype "passive"))
      (node (ref "R34") (pin "1") (pinfunction "1_1") (pintype "passive"))
      (node (ref "U10") (pin "5") (pinfunction "SDA_5") (pintype "bidirectional"))
    )
    (net (code "47") (name "PB3_MOSI") (class "Default")
      (node (ref "C24") (pin "2") (pinfunction "2_2") (pintype "passive"))
      (node (ref "J10") (pin "4") (pinfunction "4_4") (pintype "passive"))
      (node (ref "J3") (pin "3") (pinfunction "3_3") (pintype "passive"))
      (node (ref "U1") (pin "15") (pinfunction "PB3(MOSI/OC2)_15") (pintype "bidirectional"))
    )
    (net (code "48") (name "PB4_MISO") (class "Default")
      (node (ref "C26") (pin "1") (pinfunction "1_1") (pintype "passive"))
      (node (ref "C27") (pin "1") (pinfunction "1_1") (pintype "passive"))
      (node (ref "J10") (pin "1") (pinfunction "1_1") (pintype "passive"))
      (node (ref "J3") (pin "4") (pinfunction "4_4") (pintype "passive"))
      (node (ref "R21") (pin "1") (pinfunction "1_1") (pintype "passive"))
      (node (ref "U1") (pin "16") (pinfunction "PB4(MISO)_16") (pintype "bidirectional"))
    )
    (net (code "49") (name "PB5_SCK") (class "Default")
      (node (ref "J10") (pin "3") (pinfunction "3_3") (pintype "passive"))
      (node (ref "J3") (pin "5") (pinfunction "5_5") (pintype "passive"))
      (node (ref "U1") (pin "17") (pinfunction "PB5(SCK)_17") (pintype "bidirectional"))
    )
    (net (code "50") (name "PC0_ADC0") (class "Default")
      (node (ref "C13") (pin "2") (pinfunction "2_2") (pintype "passive"))
      (node (ref "J12") (pin "1") (pinfunction "1_1") (pintype "passive"))
      (node (ref "J3") (pin "9") (pinfunction "9_9") (pintype "passive"))
      (node (ref "R10") (pin "1") (pinfunction "1_1") (pintype "passive"))
      (node (ref "R11") (pin "2") (pinfunction "2_2") (pintype "passive"))
      (node (ref "U1") (pin "23") (pinfunction "PC0(ADC0)_23") (pintype "bidirectional"))
    )
    (net (code "51") (name "PC1_ADC1") (class "Default")
      (node (ref "C14") (pin "2") (pinfunction "2_2") (pintype "passive"))
      (node (ref "J11") (pin "1") (pinfunction "1_1") (pintype "passive"))
      (node (ref "J3") (pin "10") (pinfunction "10_10") (pintype "passive"))
      (node (ref "R12") (pin "1") (pinfunction "1_1") (pintype "passive"))
      (node (ref "R13") (pin "2") (pinfunction "2_2") (pintype "passive"))
      (node (ref "U1") (pin "24") (pinfunction "PC1(ADC1)_24") (pintype "bidirectional"))
    )
    (net (code "52") (name "PC3_ADC3") (class "Default")
      (node (ref "J3") (pin "11") (pinfunction "11_11") (pintype "passive"))
      (node (ref "U1") (pin "26") (pinfunction "PC3(ADC3)_26") (pintype "bidirectional"))
    )
    (net (code "53") (name "PC4_SDA") (class "Default")
      (node (ref "J3") (pin "12") (pinfunction "12_12") (pintype "passive"))
      (node (ref "J9") (pin "1") (pinfunction "1_1") (pintype "passive"))
      (node (ref "R34") (pin "2") (pinfunction "2_2") (pintype "passive"))
      (node (ref "U1") (pin "27") (pinfunction "PC4(ADC4/SDA)_27") (pintype "bidirectional"))
    )
    (net (code "54") (name "PC5_SCL") (class "Default")
      (node (ref "J3") (pin "13") (pinfunction "13_13") (pintype "passive"))
      (node (ref "J8") (pin "1") (pinfunction "1_1") (pintype "passive"))
      (node (ref "R33") (pin "2") (pinfunction "2_2") (pintype "passive"))
      (node (ref "U1") (pin "28") (pinfunction "PC5(ADC5/SCL)_28") (pintype "bidirectional"))
    )
    (net (code "55") (name "PC6_RESET") (class "Default")
      (node (ref "C32") (pin "1") (pinfunction "1_1") (pintype "passive"))
      (node (ref "J10") (pin "5") (pinfunction "5_5") (pintype "passive"))
      (node (ref "J3") (pin "2") (pinfunction "2_2") (pintype "passive"))
      (node (ref "R35") (pin "2") (pinfunction "2_2") (pintype "passive"))
      (node (ref "U1") (pin "29") (pinfunction "PC6(/RESET)_29") (pintype "bidirectional"))
    )
    (net (code "56") (name "PD0_RXD") (class "Default")
      (node (ref "J18") (pin "3") (pinfunction "3_3") (pintype "passive"))
      (node (ref "J2") (pin "1") (pinfunction "1_1") (pintype "bidirectional"))
      (node (ref "U1") (pin "30") (pinfunction "PD0(RXD)_30") (pintype "bidirectional"))
    )
    (net (code "57") (name "PD1_TXD") (class "Default")
      (node (ref "J18") (pin "4") (pinfunction "4_4") (pintype "passive"))
      (node (ref "J2") (pin "3") (pinfunction "3_3") (pintype "bidirectional"))
      (node (ref "U1") (pin "31") (pinfunction "PD1(TXD)_31") (pintype "bidirectional"))
    )
    (net (code "58") (name "PD2_INT0") (class "Default")
      (node (ref "J18") (pin "5") (pinfunction "5_5") (pintype "passive"))
      (node (ref "U1") (pin "32") (pinfunction "PD2(INT0)_32") (pintype "bidirectional"))
    )
    (net (code "59") (name "PD3_INT1") (class "Default")
      (node (ref "J18") (pin "6") (pinfunction "6_6") (pintype "passive"))
      (node (ref "U1") (pin "1") (pinfunction "PD3(INT1)_1") (pintype "bidirectional"))
    )
    (net (code "60") (name "PD4_XCK") (class "Default")
      (node (ref "J18") (pin "9") (pinfunction "9_9") (pintype "passive"))
      (node (ref "U1") (pin "2") (pinfunction "PD4(XCK/T0)_2") (pintype "bidirectional"))
    )
    (net (code "61") (name "PD5_T1") (class "Default")
      (node (ref "J18") (pin "10") (pinfunction "10_10") (pintype "passive"))
      (node (ref "U1") (pin "9") (pinfunction "PD5(T1)_9") (pintype "bidirectional"))
    )
    (net (code "62") (name "PD6_AIN0") (class "Default")
      (node (ref "J18") (pin "11") (pinfunction "11_11") (pintype "passive"))
      (node (ref "U1") (pin "10") (pinfunction "PD6(AIN0)_10") (pintype "bidirectional"))
    )
    (net (code "63") (name "PD7_AIN1") (class "Default")
      (node (ref "J18") (pin "12") (pinfunction "12_12") (pintype "passive"))
      (node (ref "U1") (pin "11") (pinfunction "PD7(AIN1)_11") (pintype "bidirectional"))
    )
    (net (code "64") (name "RX_RF") (class "Default")
      (node (ref "C23") (pin "1") (pinfunction "1_1") (pintype "passive"))
      (node (ref "J14") (pin "1") (pinfunction "1_1") (pintype "passive"))
      (node (ref "J18") (pin "13") (pinfunction "13_13") (pintype "passive"))
    )
    (net (code "65") (name "TO_FST") (class "Default")
      (node (ref "C1") (pin "1") (pinfunction "1_1") (pintype "passive"))
      (node (ref "Q1") (pin "2") (pinfunction "S_2") (pintype "bidirectional"))
      (node (ref "R16") (pin "2") (pinfunction "2_2") (pintype "passive"))
    )
    (net (code "66") (name "VCC") (class "Default")
      (node (ref "J1") (pin "1") (pinfunction "1_1") (pintype "passive"))
      (node (ref "J10") (pin "2") (pinfunction "2_2") (pintype "passive"))
      (node (ref "J2") (pin "2") (pinfunction "2_2") (pintype "bidirectional"))
      (node (ref "J3") (pin "6") (pinfunction "6_6") (pintype "passive"))
      (node (ref "L1") (pin "2") (pinfunction "2_2") (pintype "passive"))
      (node (ref "R22") (pin "1") (pinfunction "1_1") (pintype "passive"))
      (node (ref "R24") (pin "1") (pinfunction "1_1") (pintype "passive"))
      (node (ref "R25") (pin "1") (pinfunction "1_1") (pintype "passive"))
      (node (ref "R35") (pin "1") (pinfunction "1_1") (pintype "passive"))
      (node (ref "U3") (pin "3") (pinfunction "VIN_3") (pintype "passive"))
    )
    (net (code "67") (name "XA") (class "Default")
      (node (ref "C31") (pin "2") (pinfunction "2_2") (pintype "passive"))
      (node (ref "J7") (pin "1") (pinfunction "1_1") (pintype "passive"))
      (node (ref "R31") (pin "2") (pinfunction "2_2") (pintype "passive"))
      (node (ref "U10") (pin "2") (pinfunction "XA_2") (pintype "input"))
    )
    (net (code "68") (name "XB") (class "Default")
      (node (ref "J17") (pin "1") (pinfunction "1_1") (pintype "passive"))
      (node (ref "U10") (pin "3") (pinfunction "XB_3") (pintype "input"))
    )
    (net (code "69") (name "unconnected-(IC2-1A-Pad7)") (class "Default")
      (node (ref "IC2") (pin "7") (pinfunction "1A_7") (pintype "bidirectional"))
    )
    (net (code "70") (name "unconnected-(IC2-1B1-Pad6)") (class "Default")
      (node (ref "IC2") (pin "6") (pinfunction "1B1_6") (pintype "bidirectional"))
    )
    (net (code "71") (name "unconnected-(IC2-1B2-Pad5)") (class "Default")
      (node (ref "IC2") (pin "5") (pinfunction "1B2_5") (pintype "bidirectional"))
    )
    (net (code "72") (name "unconnected-(IC2-1B3-Pad4)") (class "Default")
      (node (ref "IC2") (pin "4") (pinfunction "1B3_4") (pintype "bidirectional"))
    )
    (net (code "73") (name "unconnected-(IC2-1B4-Pad3)") (class "Default")
      (node (ref "IC2") (pin "3") (pinfunction "1B4_3") (pintype "bidirectional"))
    )
    (net (code "74") (name "unconnected-(IC3-~{O1}-Pad6)") (class "Default")
      (node (ref "IC3") (pin "6") (pinfunction "~{O1}_6") (pintype "bidirectional"))
    )
    (net (code "75") (name "unconnected-(IC3-~{O3}-Pad8)") (class "Default")
      (node (ref "IC3") (pin "8") (pinfunction "~{O3}_8") (pintype "bidirectional"))
    )
    (net (code "76") (name "unconnected-(J2-Pad5)") (class "Default")
      (node (ref "J2") (pin "5") (pinfunction "5_5") (pintype "bidirectional"))
    )
    (net (code "77") (name "unconnected-(J19-Pad3)") (class "Default")
      (node (ref "J19") (pin "3") (pinfunction "3_3") (pintype "passive"))
    )
  )
)
